# cell_ballance_r.net
KiCad netlist of a schematic drawn in Altium Designer
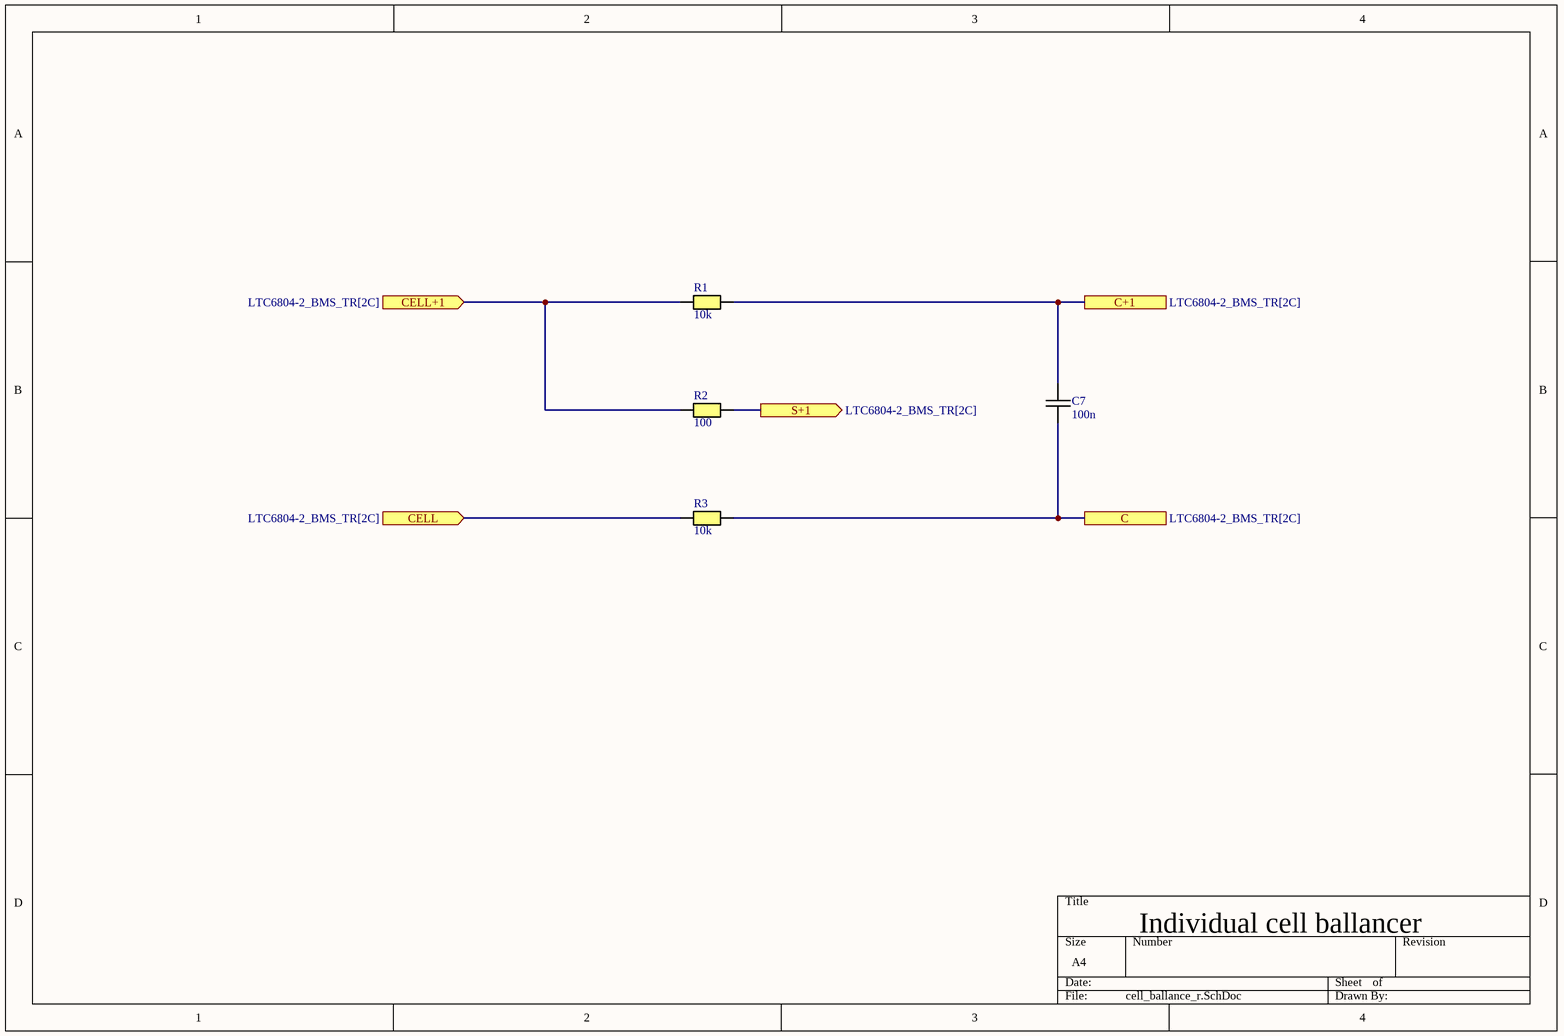
[diagram p0: cell_ballance_r.SchDoc]

(export (version "E")
  (design (tool "Eeschema 10.0.6"))
  (components
    (comp (ref "C7")
      (value "100n")
      (footprint "CAPC0603(1608)55_N")
      (description "Ceramic capacitor Medium density")
      (libsource (lib "Discrete") (part "Capacitor M"))
    )
    (comp (ref "R1")
      (value "10k")
      (footprint "RESC0603(1608)_N")
      (description "Resistor Medium Density")
      (libsource (lib "Discrete") (part "Resistor M"))
    )
    (comp (ref "R2")
      (value "100")
      (footprint "RESC0805(2012)_N")
      (description "Resistor Medium Density")
      (libsource (lib "Discrete") (part "Resistor M"))
    )
    (comp (ref "R3")
      (value "10k")
      (footprint "RESC0603(1608)_N")
      (description "Resistor Medium Density")
      (libsource (lib "Discrete") (part "Resistor M"))
    )
  )
  (nets
    (net (code "1") (name "/C") (class "Default")
      (node (ref "C7") (pin "2") (pinfunction "2_2") (pintype "passive"))
      (node (ref "R3") (pin "2") (pinfunction "2_2") (pintype "passive"))
    )
    (net (code "2") (name "/C+1") (class "Default")
      (node (ref "C7") (pin "1") (pinfunction "1_1") (pintype "passive"))
      (node (ref "R1") (pin "2") (pinfunction "2_2") (pintype "passive"))
    )
    (net (code "3") (name "/CELL") (class "Default")
      (node (ref "R3") (pin "1") (pinfunction "1_1") (pintype "passive"))
    )
    (net (code "4") (name "/CELL+1") (class "Default")
      (node (ref "R1") (pin "1") (pinfunction "1_1") (pintype "passive"))
      (node (ref "R2") (pin "1") (pinfunction "1_1") (pintype "passive"))
    )
    (net (code "5") (name "/S+1") (class "Default")
      (node (ref "R2") (pin "2") (pinfunction "2_2") (pintype "passive"))
    )
  )
)
